# ExoProg.net
KiCad netlist of a schematic drawn in EAGLE
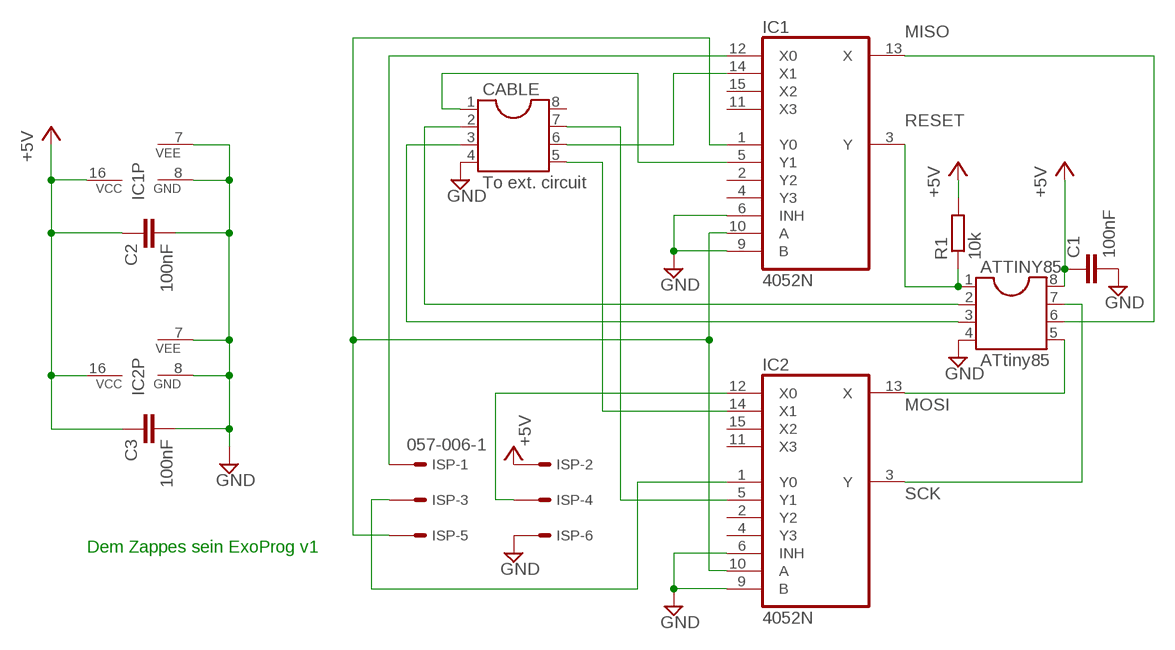
[diagram p0: schematic, sheet 1]

(export (version "E")
  (design (tool "Eeschema 10.0.6"))
  (components
    (comp (ref "ATTINY85")
      (value "ATtiny85")
      (footprint "eagle-import:DIL08")
      (libsource (lib "eagle-import") (part "DIL8"))
    )
    (comp (ref "C1")
      (value "100nF")
      (footprint "eagle-import:C2.5-3")
      (libsource (lib "eagle-import") (part "C2,5-3"))
    )
    (comp (ref "C2")
      (value "100nF")
      (footprint "eagle-import:C2.5-3")
      (libsource (lib "eagle-import") (part "C2,5-3"))
    )
    (comp (ref "C3")
      (value "100nF")
      (footprint "eagle-import:C2.5-3")
      (libsource (lib "eagle-import") (part "C2,5-3"))
    )
    (comp (ref "CABLE")
      (value "To ext. circuit")
      (footprint "eagle-import:DIL08")
      (libsource (lib "eagle-import") (part "DIL8"))
    )
    (comp (ref "IC1")
      (value "4052N")
      (footprint "eagle-import:DIL16")
      (libsource (lib "eagle-import") (part "4052N"))
    )
    (comp (ref "IC2")
      (value "4052N")
      (footprint "eagle-import:DIL16")
      (libsource (lib "eagle-import") (part "4052N"))
    )
    (comp (ref "ISP")
      (value "057-006-1")
      (footprint "eagle-import:057-006-1")
      (libsource (lib "eagle-import") (part "057-006-1"))
    )
    (comp (ref "R1")
      (value "10k")
      (footprint "eagle-import:0207_10")
      (libsource (lib "eagle-import") (part "R-EU_0207/10"))
    )
  )
  (nets
    (net (code "1") (name "+5V") (class "Default")
      (node (ref "ATTINY85") (pin "8") (pinfunction "8_8") (pintype "passive"))
      (node (ref "C1") (pin "1") (pinfunction "1_1") (pintype "passive"))
      (node (ref "C2") (pin "1") (pinfunction "1_1") (pintype "passive"))
      (node (ref "C3") (pin "1") (pinfunction "1_1") (pintype "passive"))
      (node (ref "IC1") (pin "16") (pinfunction "VCC_16") (pintype "power_in"))
      (node (ref "IC2") (pin "16") (pinfunction "VCC_16") (pintype "power_in"))
      (node (ref "ISP") (pin "2") (pinfunction "S_2") (pintype "passive"))
      (node (ref "R1") (pin "2") (pinfunction "2_2") (pintype "passive"))
    )
    (net (code "2") (name "/MISO") (class "Default")
      (node (ref "ATTINY85") (pin "6") (pinfunction "6_6") (pintype "passive"))
      (node (ref "IC1") (pin "13") (pinfunction "X_13") (pintype "bidirectional"))
    )
    (net (code "3") (name "/MOSI") (class "Default")
      (node (ref "ATTINY85") (pin "5") (pinfunction "5_5") (pintype "passive"))
      (node (ref "IC2") (pin "13") (pinfunction "X_13") (pintype "bidirectional"))
    )
    (net (code "4") (name "/RESET") (class "Default")
      (node (ref "ATTINY85") (pin "1") (pinfunction "1_1") (pintype "passive"))
      (node (ref "IC1") (pin "3") (pinfunction "Y_3") (pintype "bidirectional"))
      (node (ref "R1") (pin "1") (pinfunction "1_1") (pintype "passive"))
    )
    (net (code "5") (name "/SCK") (class "Default")
      (node (ref "ATTINY85") (pin "7") (pinfunction "7_7") (pintype "passive"))
      (node (ref "IC2") (pin "3") (pinfunction "Y_3") (pintype "bidirectional"))
    )
    (net (code "6") (name "GND") (class "Default")
      (node (ref "ATTINY85") (pin "4") (pinfunction "4_4") (pintype "passive"))
      (node (ref "C1") (pin "2") (pinfunction "2_2") (pintype "passive"))
      (node (ref "C2") (pin "2") (pinfunction "2_2") (pintype "passive"))
      (node (ref "C3") (pin "2") (pinfunction "2_2") (pintype "passive"))
      (node (ref "CABLE") (pin "4") (pinfunction "4_4") (pintype "passive"))
      (node (ref "IC1") (pin "6") (pinfunction "INH_6") (pintype "input"))
      (node (ref "IC1") (pin "7") (pinfunction "VEE_7") (pintype "power_in"))
      (node (ref "IC1") (pin "8") (pinfunction "GND_8") (pintype "power_in"))
      (node (ref "IC1") (pin "9") (pinfunction "B_9") (pintype "input"))
      (node (ref "IC2") (pin "6") (pinfunction "INH_6") (pintype "input"))
      (node (ref "IC2") (pin "7") (pinfunction "VEE_7") (pintype "power_in"))
      (node (ref "IC2") (pin "8") (pinfunction "GND_8") (pintype "power_in"))
      (node (ref "IC2") (pin "9") (pinfunction "B_9") (pintype "input"))
      (node (ref "ISP") (pin "6") (pinfunction "S_6") (pintype "passive"))
    )
    (net (code "7") (name "Net-(ATTINY85-Pad2)") (class "Default")
      (node (ref "ATTINY85") (pin "2") (pinfunction "2_2") (pintype "passive"))
      (node (ref "CABLE") (pin "2") (pinfunction "2_2") (pintype "passive"))
    )
    (net (code "8") (name "Net-(ATTINY85-Pad3)") (class "Default")
      (node (ref "ATTINY85") (pin "3") (pinfunction "3_3") (pintype "passive"))
      (node (ref "CABLE") (pin "3") (pinfunction "3_3") (pintype "passive"))
    )
    (net (code "9") (name "Net-(IC1A-A)") (class "Default")
      (node (ref "IC1") (pin "1") (pinfunction "Y0_1") (pintype "bidirectional"))
      (node (ref "IC1") (pin "10") (pinfunction "A_10") (pintype "input"))
      (node (ref "IC2") (pin "10") (pinfunction "A_10") (pintype "input"))
      (node (ref "ISP") (pin "5") (pinfunction "S_5") (pintype "passive"))
    )
    (net (code "10") (name "Net-(IC1A-X0)") (class "Default")
      (node (ref "IC1") (pin "12") (pinfunction "X0_12") (pintype "bidirectional"))
      (node (ref "ISP") (pin "1") (pinfunction "S_1") (pintype "passive"))
    )
    (net (code "11") (name "Net-(IC1A-X1)") (class "Default")
      (node (ref "CABLE") (pin "6") (pinfunction "6_6") (pintype "passive"))
      (node (ref "IC1") (pin "14") (pinfunction "X1_14") (pintype "bidirectional"))
    )
    (net (code "12") (name "Net-(IC1A-Y1)") (class "Default")
      (node (ref "CABLE") (pin "1") (pinfunction "1_1") (pintype "passive"))
      (node (ref "IC1") (pin "5") (pinfunction "Y1_5") (pintype "bidirectional"))
    )
    (net (code "13") (name "Net-(IC2A-X0)") (class "Default")
      (node (ref "IC2") (pin "12") (pinfunction "X0_12") (pintype "bidirectional"))
      (node (ref "ISP") (pin "4") (pinfunction "S_4") (pintype "passive"))
    )
    (net (code "14") (name "Net-(IC2A-X1)") (class "Default")
      (node (ref "CABLE") (pin "5") (pinfunction "5_5") (pintype "passive"))
      (node (ref "IC2") (pin "14") (pinfunction "X1_14") (pintype "bidirectional"))
    )
    (net (code "15") (name "Net-(IC2A-Y0)") (class "Default")
      (node (ref "IC2") (pin "1") (pinfunction "Y0_1") (pintype "bidirectional"))
      (node (ref "ISP") (pin "3") (pinfunction "S_3") (pintype "passive"))
    )
    (net (code "16") (name "Net-(IC2A-Y1)") (class "Default")
      (node (ref "CABLE") (pin "7") (pinfunction "7_7") (pintype "passive"))
      (node (ref "IC2") (pin "5") (pinfunction "Y1_5") (pintype "bidirectional"))
    )
    (net (code "17") (name "unconnected-(CABLE-Pad8)") (class "Default")
      (node (ref "CABLE") (pin "8") (pinfunction "8_8") (pintype "passive"))
    )
    (net (code "18") (name "unconnected-(IC1A-X2-Pad15)") (class "Default")
      (node (ref "IC1") (pin "15") (pinfunction "X2_15") (pintype "bidirectional"))
    )
    (net (code "19") (name "unconnected-(IC1A-X3-Pad11)") (class "Default")
      (node (ref "IC1") (pin "11") (pinfunction "X3_11") (pintype "bidirectional"))
    )
    (net (code "20") (name "unconnected-(IC1A-Y2-Pad2)") (class "Default")
      (node (ref "IC1") (pin "2") (pinfunction "Y2_2") (pintype "bidirectional"))
    )
    (net (code "21") (name "unconnected-(IC1A-Y3-Pad4)") (class "Default")
      (node (ref "IC1") (pin "4") (pinfunction "Y3_4") (pintype "bidirectional"))
    )
    (net (code "22") (name "unconnected-(IC2A-X2-Pad15)") (class "Default")
      (node (ref "IC2") (pin "15") (pinfunction "X2_15") (pintype "bidirectional"))
    )
    (net (code "23") (name "unconnected-(IC2A-X3-Pad11)") (class "Default")
      (node (ref "IC2") (pin "11") (pinfunction "X3_11") (pintype "bidirectional"))
    )
    (net (code "24") (name "unconnected-(IC2A-Y2-Pad2)") (class "Default")
      (node (ref "IC2") (pin "2") (pinfunction "Y2_2") (pintype "bidirectional"))
    )
    (net (code "25") (name "unconnected-(IC2A-Y3-Pad4)") (class "Default")
      (node (ref "IC2") (pin "4") (pinfunction "Y3_4") (pintype "bidirectional"))
    )
  )
)
